# Negative_Ioniser.net
KiCad netlist of a schematic drawn in EAGLE
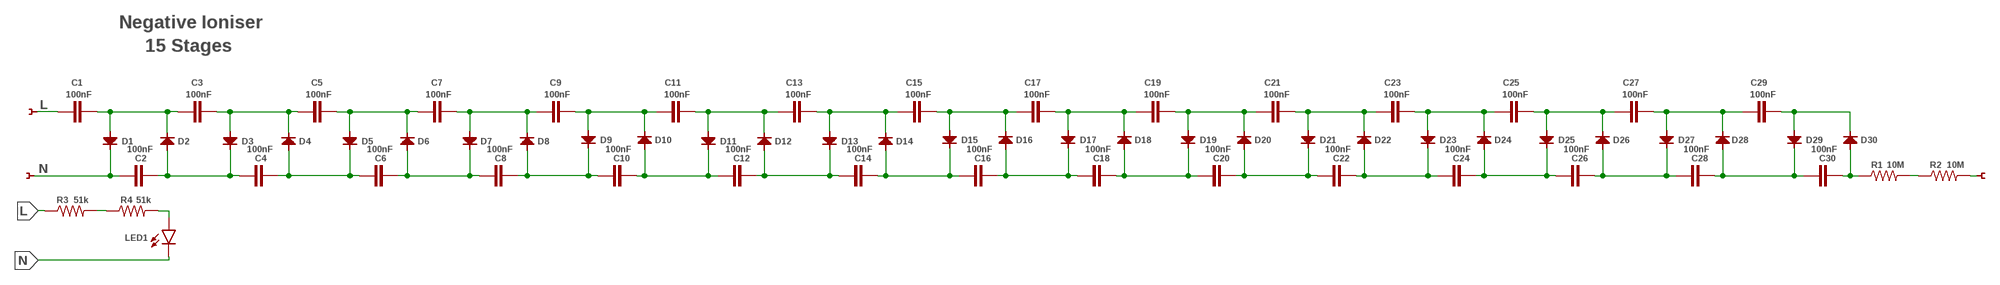
[diagram p0: schematic, sheet 1]

(export (version "E")
  (design (tool "Eeschema 10.0.6"))
  (components
    (comp (ref "C1")
      (value "100nF")
      (footprint "eagle-import:C1812")
      (fields (field (name "TOLERANCE") "±10%"))
      (libsource (lib "eagle-import") (part "CAPACITOR-1812"))
    )
    (comp (ref "C2")
      (value "100nF")
      (footprint "eagle-import:C1812")
      (fields
        (field (name "PART-NUM") "1812B104K631CT")
        (field (name "RATED") "630V")
        (field (name "TOLERANCE") "±10%")
      )
      (libsource (lib "eagle-import") (part "CAPACITOR-1812"))
    )
    (comp (ref "C3")
      (value "100nF")
      (footprint "eagle-import:C1812")
      (fields
        (field (name "PART-NUM") "1812B104K631CT")
        (field (name "RATED") "630V")
        (field (name "TOLERANCE") "±10%")
      )
      (libsource (lib "eagle-import") (part "CAPACITOR-1812"))
    )
    (comp (ref "C4")
      (value "100nF")
      (footprint "eagle-import:C1812")
      (fields
        (field (name "PART-NUM") "1812B104K631CT")
        (field (name "RATED") "630V")
        (field (name "TOLERANCE") "±10%")
      )
      (libsource (lib "eagle-import") (part "CAPACITOR-1812"))
    )
    (comp (ref "C5")
      (value "100nF")
      (footprint "eagle-import:C1812")
      (fields (field (name "TOLERANCE") "±10%"))
      (libsource (lib "eagle-import") (part "CAPACITOR-1812"))
    )
    (comp (ref "C6")
      (value "100nF")
      (footprint "eagle-import:C1812")
      (fields
        (field (name "PART-NUM") "1812B104K631CT")
        (field (name "RATED") "630V")
        (field (name "TOLERANCE") "±10%")
      )
      (libsource (lib "eagle-import") (part "CAPACITOR-1812"))
    )
    (comp (ref "C7")
      (value "100nF")
      (footprint "eagle-import:C1812")
      (fields
        (field (name "PART-NUM") "1812B104K631CT")
        (field (name "RATED") "630V")
        (field (name "TOLERANCE") "±10%")
      )
      (libsource (lib "eagle-import") (part "CAPACITOR-1812"))
    )
    (comp (ref "C8")
      (value "100nF")
      (footprint "eagle-import:C1812")
      (fields
        (field (name "PART-NUM") "1812B104K631CT")
        (field (name "RATED") "630V")
        (field (name "TOLERANCE") "±10%")
      )
      (libsource (lib "eagle-import") (part "CAPACITOR-1812"))
    )
    (comp (ref "C9")
      (value "100nF")
      (footprint "eagle-import:C1812")
      (fields (field (name "TOLERANCE") "±10%"))
      (libsource (lib "eagle-import") (part "CAPACITOR-1812"))
    )
    (comp (ref "C10")
      (value "100nF")
      (footprint "eagle-import:C1812")
      (fields
        (field (name "PART-NUM") "1812B104K631CT")
        (field (name "RATED") "630V")
        (field (name "TOLERANCE") "±10%")
      )
      (libsource (lib "eagle-import") (part "CAPACITOR-1812"))
    )
    (comp (ref "C11")
      (value "100nF")
      (footprint "eagle-import:C1812")
      (fields
        (field (name "PART-NUM") "1812B104K631CT")
        (field (name "RATED") "630V")
        (field (name "TOLERANCE") "±10%")
      )
      (libsource (lib "eagle-import") (part "CAPACITOR-1812"))
    )
    (comp (ref "C12")
      (value "100nF")
      (footprint "eagle-import:C1812")
      (fields
        (field (name "PART-NUM") "1812B104K631CT")
        (field (name "RATED") "630V")
        (field (name "TOLERANCE") "±10%")
      )
      (libsource (lib "eagle-import") (part "CAPACITOR-1812"))
    )
    (comp (ref "C13")
      (value "100nF")
      (footprint "eagle-import:C1812")
      (fields (field (name "TOLERANCE") "±10%"))
      (libsource (lib "eagle-import") (part "CAPACITOR-1812"))
    )
    (comp (ref "C14")
      (value "100nF")
      (footprint "eagle-import:C1812")
      (fields
        (field (name "PART-NUM") "1812B104K631CT")
        (field (name "RATED") "630V")
        (field (name "TOLERANCE") "±10%")
      )
      (libsource (lib "eagle-import") (part "CAPACITOR-1812"))
    )
    (comp (ref "C15")
      (value "100nF")
      (footprint "eagle-import:C1812")
      (fields
        (field (name "PART-NUM") "1812B104K631CT")
        (field (name "RATED") "630V")
        (field (name "TOLERANCE") "±10%")
      )
      (libsource (lib "eagle-import") (part "CAPACITOR-1812"))
    )
    (comp (ref "C16")
      (value "100nF")
      (footprint "eagle-import:C1812")
      (fields
        (field (name "PART-NUM") "1812B104K631CT")
        (field (name "RATED") "630V")
        (field (name "TOLERANCE") "±10%")
      )
      (libsource (lib "eagle-import") (part "CAPACITOR-1812"))
    )
    (comp (ref "C17")
      (value "100nF")
      (footprint "eagle-import:C1812")
      (fields (field (name "TOLERANCE") "±10%"))
      (libsource (lib "eagle-import") (part "CAPACITOR-1812"))
    )
    (comp (ref "C18")
      (value "100nF")
      (footprint "eagle-import:C1812")
      (fields
        (field (name "PART-NUM") "1812B104K631CT")
        (field (name "RATED") "630V")
        (field (name "TOLERANCE") "±10%")
      )
      (libsource (lib "eagle-import") (part "CAPACITOR-1812"))
    )
    (comp (ref "C19")
      (value "100nF")
      (footprint "eagle-import:C1812")
      (fields
        (field (name "PART-NUM") "1812B104K631CT")
        (field (name "RATED") "630V")
        (field (name "TOLERANCE") "±10%")
      )
      (libsource (lib "eagle-import") (part "CAPACITOR-1812"))
    )
    (comp (ref "C20")
      (value "100nF")
      (footprint "eagle-import:C1812")
      (fields
        (field (name "PART-NUM") "1812B104K631CT")
        (field (name "RATED") "630V")
        (field (name "TOLERANCE") "±10%")
      )
      (libsource (lib "eagle-import") (part "CAPACITOR-1812"))
    )
    (comp (ref "C21")
      (value "100nF")
      (footprint "eagle-import:C1812")
      (fields (field (name "TOLERANCE") "±10%"))
      (libsource (lib "eagle-import") (part "CAPACITOR-1812"))
    )
    (comp (ref "C22")
      (value "100nF")
      (footprint "eagle-import:C1812")
      (fields
        (field (name "PART-NUM") "1812B104K631CT")
        (field (name "RATED") "630V")
        (field (name "TOLERANCE") "±10%")
      )
      (libsource (lib "eagle-import") (part "CAPACITOR-1812"))
    )
    (comp (ref "C23")
      (value "100nF")
      (footprint "eagle-import:C1812")
      (fields
        (field (name "PART-NUM") "1812B104K631CT")
        (field (name "RATED") "630V")
        (field (name "TOLERANCE") "±10%")
      )
      (libsource (lib "eagle-import") (part "CAPACITOR-1812"))
    )
    (comp (ref "C24")
      (value "100nF")
      (footprint "eagle-import:C1812")
      (fields
        (field (name "PART-NUM") "1812B104K631CT")
        (field (name "RATED") "630V")
        (field (name "TOLERANCE") "±10%")
      )
      (libsource (lib "eagle-import") (part "CAPACITOR-1812"))
    )
    (comp (ref "C25")
      (value "100nF")
      (footprint "eagle-import:C1812")
      (fields (field (name "TOLERANCE") "±10%"))
      (libsource (lib "eagle-import") (part "CAPACITOR-1812"))
    )
    (comp (ref "C26")
      (value "100nF")
      (footprint "eagle-import:C1812")
      (fields
        (field (name "PART-NUM") "1812B104K631CT")
        (field (name "RATED") "630V")
        (field (name "TOLERANCE") "±10%")
      )
      (libsource (lib "eagle-import") (part "CAPACITOR-1812"))
    )
    (comp (ref "C27")
      (value "100nF")
      (footprint "eagle-import:C1812")
      (fields
        (field (name "PART-NUM") "1812B104K631CT")
        (field (name "RATED") "630V")
        (field (name "TOLERANCE") "±10%")
      )
      (libsource (lib "eagle-import") (part "CAPACITOR-1812"))
    )
    (comp (ref "C28")
      (value "100nF")
      (footprint "eagle-import:C1812")
      (fields
        (field (name "PART-NUM") "1812B104K631CT")
        (field (name "RATED") "630V")
        (field (name "TOLERANCE") "±10%")
      )
      (libsource (lib "eagle-import") (part "CAPACITOR-1812"))
    )
    (comp (ref "C29")
      (value "100nF")
      (footprint "eagle-import:C1812")
      (fields
        (field (name "PART-NUM") "1812B104K631CT")
        (field (name "RATED") "630V")
        (field (name "TOLERANCE") "±10%")
      )
      (libsource (lib "eagle-import") (part "CAPACITOR-1812"))
    )
    (comp (ref "C30")
      (value "100nF")
      (footprint "eagle-import:C1812")
      (fields
        (field (name "PART-NUM") "1812B104K631CT")
        (field (name "RATED") "630V")
        (field (name "TOLERANCE") "±10%")
      )
      (libsource (lib "eagle-import") (part "CAPACITOR-1812"))
    )
    (comp (ref "D1")
      (value "DIODE-1N4007")
      (footprint "eagle-import:DO-214A")
      (fields
        (field (name "I-RATING") "1A")
        (field (name "PART-NUM") "1N4007G")
        (field (name "V-RATING") "1kV")
      )
      (libsource (lib "eagle-import") (part "DIODE-1N4007"))
    )
    (comp (ref "D2")
      (value "DIODE-1N4007")
      (footprint "eagle-import:DO-214A")
      (fields
        (field (name "I-RATING") "1A")
        (field (name "PART-NUM") "1N4007G")
        (field (name "V-RATING") "1kV")
      )
      (libsource (lib "eagle-import") (part "DIODE-1N4007"))
    )
    (comp (ref "D3")
      (value "DIODE-1N4007")
      (footprint "eagle-import:DO-214A")
      (fields
        (field (name "I-RATING") "1A")
        (field (name "PART-NUM") "1N4007G")
        (field (name "V-RATING") "1kV")
      )
      (libsource (lib "eagle-import") (part "DIODE-1N4007"))
    )
    (comp (ref "D4")
      (value "DIODE-1N4007")
      (footprint "eagle-import:DO-214A")
      (fields
        (field (name "I-RATING") "1A")
        (field (name "PART-NUM") "1N4007G")
        (field (name "V-RATING") "1kV")
      )
      (libsource (lib "eagle-import") (part "DIODE-1N4007"))
    )
    (comp (ref "D5")
      (value "DIODE-1N4007")
      (footprint "eagle-import:DO-214A")
      (fields
        (field (name "I-RATING") "1A")
        (field (name "PART-NUM") "1N4007G")
        (field (name "V-RATING") "1kV")
      )
      (libsource (lib "eagle-import") (part "DIODE-1N4007"))
    )
    (comp (ref "D6")
      (value "DIODE-1N4007")
      (footprint "eagle-import:DO-214A")
      (fields
        (field (name "I-RATING") "1A")
        (field (name "PART-NUM") "1N4007G")
        (field (name "V-RATING") "1kV")
      )
      (libsource (lib "eagle-import") (part "DIODE-1N4007"))
    )
    (comp (ref "D7")
      (value "DIODE-1N4007")
      (footprint "eagle-import:DO-214A")
      (fields
        (field (name "I-RATING") "1A")
        (field (name "PART-NUM") "1N4007G")
        (field (name "V-RATING") "1kV")
      )
      (libsource (lib "eagle-import") (part "DIODE-1N4007"))
    )
    (comp (ref "D8")
      (value "DIODE-1N4007")
      (footprint "eagle-import:DO-214A")
      (fields
        (field (name "I-RATING") "1A")
        (field (name "PART-NUM") "1N4007G")
        (field (name "V-RATING") "1kV")
      )
      (libsource (lib "eagle-import") (part "DIODE-1N4007"))
    )
    (comp (ref "D9")
      (value "DIODE-1N4007")
      (footprint "eagle-import:DO-214A")
      (fields
        (field (name "I-RATING") "1A")
        (field (name "PART-NUM") "1N4007G")
        (field (name "V-RATING") "1kV")
      )
      (libsource (lib "eagle-import") (part "DIODE-1N4007"))
    )
    (comp (ref "D10")
      (value "DIODE-1N4007")
      (footprint "eagle-import:DO-214A")
      (fields
        (field (name "I-RATING") "1A")
        (field (name "PART-NUM") "1N4007G")
        (field (name "V-RATING") "1kV")
      )
      (libsource (lib "eagle-import") (part "DIODE-1N4007"))
    )
    (comp (ref "D11")
      (value "DIODE-1N4007")
      (footprint "eagle-import:DO-214A")
      (fields
        (field (name "I-RATING") "1A")
        (field (name "PART-NUM") "1N4007G")
        (field (name "V-RATING") "1kV")
      )
      (libsource (lib "eagle-import") (part "DIODE-1N4007"))
    )
    (comp (ref "D12")
      (value "DIODE-1N4007")
      (footprint "eagle-import:DO-214A")
      (fields
        (field (name "I-RATING") "1A")
        (field (name "PART-NUM") "1N4007G")
        (field (name "V-RATING") "1kV")
      )
      (libsource (lib "eagle-import") (part "DIODE-1N4007"))
    )
    (comp (ref "D13")
      (value "DIODE-1N4007")
      (footprint "eagle-import:DO-214A")
      (fields
        (field (name "I-RATING") "1A")
        (field (name "PART-NUM") "1N4007G")
        (field (name "V-RATING") "1kV")
      )
      (libsource (lib "eagle-import") (part "DIODE-1N4007"))
    )
    (comp (ref "D14")
      (value "DIODE-1N4007")
      (footprint "eagle-import:DO-214A")
      (fields
        (field (name "I-RATING") "1A")
        (field (name "PART-NUM") "1N4007G")
        (field (name "V-RATING") "1kV")
      )
      (libsource (lib "eagle-import") (part "DIODE-1N4007"))
    )
    (comp (ref "D15")
      (value "DIODE-1N4007")
      (footprint "eagle-import:DO-214A")
      (fields
        (field (name "I-RATING") "1A")
        (field (name "PART-NUM") "1N4007G")
        (field (name "V-RATING") "1kV")
      )
      (libsource (lib "eagle-import") (part "DIODE-1N4007"))
    )
    (comp (ref "D16")
      (value "DIODE-1N4007")
      (footprint "eagle-import:DO-214A")
      (fields
        (field (name "I-RATING") "1A")
        (field (name "PART-NUM") "1N4007G")
        (field (name "V-RATING") "1kV")
      )
      (libsource (lib "eagle-import") (part "DIODE-1N4007"))
    )
    (comp (ref "D17")
      (value "DIODE-1N4007")
      (footprint "eagle-import:DO-214A")
      (fields
        (field (name "I-RATING") "1A")
        (field (name "PART-NUM") "1N4007G")
        (field (name "V-RATING") "1kV")
      )
      (libsource (lib "eagle-import") (part "DIODE-1N4007"))
    )
    (comp (ref "D18")
      (value "DIODE-1N4007")
      (footprint "eagle-import:DO-214A")
      (fields
        (field (name "I-RATING") "1A")
        (field (name "PART-NUM") "1N4007G")
        (field (name "V-RATING") "1kV")
      )
      (libsource (lib "eagle-import") (part "DIODE-1N4007"))
    )
    (comp (ref "D19")
      (value "DIODE-1N4007")
      (footprint "eagle-import:DO-214A")
      (fields
        (field (name "I-RATING") "1A")
        (field (name "PART-NUM") "1N4007G")
        (field (name "V-RATING") "1kV")
      )
      (libsource (lib "eagle-import") (part "DIODE-1N4007"))
    )
    (comp (ref "D20")
      (value "DIODE-1N4007")
      (footprint "eagle-import:DO-214A")
      (fields
        (field (name "I-RATING") "1A")
        (field (name "PART-NUM") "1N4007G")
        (field (name "V-RATING") "1kV")
      )
      (libsource (lib "eagle-import") (part "DIODE-1N4007"))
    )
    (comp (ref "D21")
      (value "DIODE-1N4007")
      (footprint "eagle-import:DO-214A")
      (fields
        (field (name "I-RATING") "1A")
        (field (name "PART-NUM") "1N4007G")
        (field (name "V-RATING") "1kV")
      )
      (libsource (lib "eagle-import") (part "DIODE-1N4007"))
    )
    (comp (ref "D22")
      (value "DIODE-1N4007")
      (footprint "eagle-import:DO-214A")
      (fields
        (field (name "I-RATING") "1A")
        (field (name "PART-NUM") "1N4007G")
        (field (name "V-RATING") "1kV")
      )
      (libsource (lib "eagle-import") (part "DIODE-1N4007"))
    )
    (comp (ref "D23")
      (value "DIODE-1N4007")
      (footprint "eagle-import:DO-214A")
      (fields
        (field (name "I-RATING") "1A")
        (field (name "PART-NUM") "1N4007G")
        (field (name "V-RATING") "1kV")
      )
      (libsource (lib "eagle-import") (part "DIODE-1N4007"))
    )
    (comp (ref "D24")
      (value "DIODE-1N4007")
      (footprint "eagle-import:DO-214A")
      (fields
        (field (name "I-RATING") "1A")
        (field (name "PART-NUM") "1N4007G")
        (field (name "V-RATING") "1kV")
      )
      (libsource (lib "eagle-import") (part "DIODE-1N4007"))
    )
    (comp (ref "D25")
      (value "DIODE-1N4007")
      (footprint "eagle-import:DO-214A")
      (fields
        (field (name "I-RATING") "1A")
        (field (name "PART-NUM") "1N4007G")
        (field (name "V-RATING") "1kV")
      )
      (libsource (lib "eagle-import") (part "DIODE-1N4007"))
    )
    (comp (ref "D26")
      (value "DIODE-1N4007")
      (footprint "eagle-import:DO-214A")
      (fields
        (field (name "I-RATING") "1A")
        (field (name "PART-NUM") "1N4007G")
        (field (name "V-RATING") "1kV")
      )
      (libsource (lib "eagle-import") (part "DIODE-1N4007"))
    )
    (comp (ref "D27")
      (value "DIODE-1N4007")
      (footprint "eagle-import:DO-214A")
      (fields
        (field (name "I-RATING") "1A")
        (field (name "PART-NUM") "1N4007G")
        (field (name "V-RATING") "1kV")
      )
      (libsource (lib "eagle-import") (part "DIODE-1N4007"))
    )
    (comp (ref "D28")
      (value "DIODE-1N4007")
      (footprint "eagle-import:DO-214A")
      (fields
        (field (name "I-RATING") "1A")
        (field (name "PART-NUM") "1N4007G")
        (field (name "V-RATING") "1kV")
      )
      (libsource (lib "eagle-import") (part "DIODE-1N4007"))
    )
    (comp (ref "D29")
      (value "DIODE-1N4007")
      (footprint "eagle-import:DO-214A")
      (fields
        (field (name "I-RATING") "1A")
        (field (name "PART-NUM") "1N4007G")
        (field (name "V-RATING") "1kV")
      )
      (libsource (lib "eagle-import") (part "DIODE-1N4007"))
    )
    (comp (ref "D30")
      (value "DIODE-1N4007")
      (footprint "eagle-import:DO-214A")
      (fields
        (field (name "I-RATING") "1A")
        (field (name "PART-NUM") "1N4007G")
        (field (name "V-RATING") "1kV")
      )
      (libsource (lib "eagle-import") (part "DIODE-1N4007"))
    )
    (comp (ref "LED1")
      (value "LED-0603-SMD")
      (footprint "eagle-import:LED-0603")
      (fields (field (name "PART-NUM") "D-060306R1/SS2/L"))
      (libsource (lib "eagle-import") (part "LED-0603-SMD"))
    )
    (comp (ref "R1")
      (value "10M")
      (footprint "eagle-import:R1206")
      (fields
        (field (name "PART-NUM") "1206W4F1005T5E")
        (field (name "RATED") "0.25W")
        (field (name "TOLERANCE") "±1%")
      )
      (libsource (lib "eagle-import") (part "RESISTOR-1206"))
    )
    (comp (ref "R2")
      (value "10M")
      (footprint "eagle-import:R1206")
      (fields
        (field (name "PART-NUM") "1206W4F1005T5E")
        (field (name "RATED") "0.25W")
        (field (name "TOLERANCE") "±1%")
      )
      (libsource (lib "eagle-import") (part "RESISTOR-1206"))
    )
    (comp (ref "R3")
      (value "51k")
      (footprint "eagle-import:R1210")
      (fields
        (field (name "PART-NUM") "CR1210J51K0P05Z")
        (field (name "RATED") "0.5W")
        (field (name "TOLERANCE") "±5%")
      )
      (libsource (lib "eagle-import") (part "RESISTOR-1210"))
    )
    (comp (ref "R4")
      (value "51k")
      (footprint "eagle-import:R1210")
      (fields
        (field (name "PART-NUM") "CR1210J51K0P05Z")
        (field (name "RATED") "0.5W")
        (field (name "TOLERANCE") "±5%")
      )
      (libsource (lib "eagle-import") (part "RESISTOR-1210"))
    )
    (comp (ref "TP1")
      (value "TEST-POINT5MM")
      (footprint "eagle-import:SMD-SQ-PADS-5MM")
      (libsource (lib "eagle-import") (part "TEST-POINT5MM"))
    )
    (comp (ref "TP2")
      (value "TEST-POINT5MM")
      (footprint "eagle-import:SMD-SQ-PADS-5MM")
      (libsource (lib "eagle-import") (part "TEST-POINT5MM"))
    )
    (comp (ref "TP3")
      (value "TEST-POINT30X10")
      (footprint "eagle-import:LONG-RECT-PAD-50MM")
      (libsource (lib "eagle-import") (part "TEST-POINT30X10"))
    )
  )
  (nets
    (net (code "1") (name "L") (class "Default")
      (node (ref "C1") (pin "1") (pinfunction "1_1") (pintype "passive"))
      (node (ref "R3") (pin "1") (pinfunction "1_1") (pintype "passive"))
      (node (ref "TP1") (pin "P$1") (pinfunction "1_P$1") (pintype "bidirectional"))
    )
    (net (code "2") (name "N") (class "Default")
      (node (ref "C2") (pin "1") (pinfunction "1_1") (pintype "passive"))
      (node (ref "D1") (pin "CATHODE") (pinfunction "C_CATHODE") (pintype "bidirectional"))
      (node (ref "LED1") (pin "C") (pinfunction "C_C") (pintype "passive"))
      (node (ref "TP2") (pin "P$1") (pinfunction "1_P$1") (pintype "bidirectional"))
    )
    (net (code "3") (name "Net-(D1-A)") (class "Default")
      (node (ref "C1") (pin "2") (pinfunction "2_2") (pintype "passive"))
      (node (ref "C3") (pin "1") (pinfunction "1_1") (pintype "passive"))
      (node (ref "D1") (pin "ANODE") (pinfunction "A_ANODE") (pintype "bidirectional"))
      (node (ref "D2") (pin "CATHODE") (pinfunction "C_CATHODE") (pintype "bidirectional"))
    )
    (net (code "4") (name "Net-(D2-A)") (class "Default")
      (node (ref "C2") (pin "2") (pinfunction "2_2") (pintype "passive"))
      (node (ref "C4") (pin "1") (pinfunction "1_1") (pintype "passive"))
      (node (ref "D2") (pin "ANODE") (pinfunction "A_ANODE") (pintype "bidirectional"))
      (node (ref "D3") (pin "CATHODE") (pinfunction "C_CATHODE") (pintype "bidirectional"))
    )
    (net (code "5") (name "Net-(D3-A)") (class "Default")
      (node (ref "C3") (pin "2") (pinfunction "2_2") (pintype "passive"))
      (node (ref "C5") (pin "1") (pinfunction "1_1") (pintype "passive"))
      (node (ref "D3") (pin "ANODE") (pinfunction "A_ANODE") (pintype "bidirectional"))
      (node (ref "D4") (pin "CATHODE") (pinfunction "C_CATHODE") (pintype "bidirectional"))
    )
    (net (code "6") (name "Net-(D4-A)") (class "Default")
      (node (ref "C4") (pin "2") (pinfunction "2_2") (pintype "passive"))
      (node (ref "C6") (pin "1") (pinfunction "1_1") (pintype "passive"))
      (node (ref "D4") (pin "ANODE") (pinfunction "A_ANODE") (pintype "bidirectional"))
      (node (ref "D5") (pin "CATHODE") (pinfunction "C_CATHODE") (pintype "bidirectional"))
    )
    (net (code "7") (name "Net-(D5-A)") (class "Default")
      (node (ref "C5") (pin "2") (pinfunction "2_2") (pintype "passive"))
      (node (ref "C7") (pin "1") (pinfunction "1_1") (pintype "passive"))
      (node (ref "D5") (pin "ANODE") (pinfunction "A_ANODE") (pintype "bidirectional"))
      (node (ref "D6") (pin "CATHODE") (pinfunction "C_CATHODE") (pintype "bidirectional"))
    )
    (net (code "8") (name "Net-(D6-A)") (class "Default")
      (node (ref "C6") (pin "2") (pinfunction "2_2") (pintype "passive"))
      (node (ref "C8") (pin "1") (pinfunction "1_1") (pintype "passive"))
      (node (ref "D6") (pin "ANODE") (pinfunction "A_ANODE") (pintype "bidirectional"))
      (node (ref "D7") (pin "CATHODE") (pinfunction "C_CATHODE") (pintype "bidirectional"))
    )
    (net (code "9") (name "Net-(D7-A)") (class "Default")
      (node (ref "C7") (pin "2") (pinfunction "2_2") (pintype "passive"))
      (node (ref "C9") (pin "1") (pinfunction "1_1") (pintype "passive"))
      (node (ref "D7") (pin "ANODE") (pinfunction "A_ANODE") (pintype "bidirectional"))
      (node (ref "D8") (pin "CATHODE") (pinfunction "C_CATHODE") (pintype "bidirectional"))
    )
    (net (code "10") (name "Net-(D8-A)") (class "Default")
      (node (ref "C10") (pin "1") (pinfunction "1_1") (pintype "passive"))
      (node (ref "C8") (pin "2") (pinfunction "2_2") (pintype "passive"))
      (node (ref "D8") (pin "ANODE") (pinfunction "A_ANODE") (pintype "bidirectional"))
      (node (ref "D9") (pin "CATHODE") (pinfunction "C_CATHODE") (pintype "bidirectional"))
    )
    (net (code "11") (name "Net-(D10-A)") (class "Default")
      (node (ref "C10") (pin "2") (pinfunction "2_2") (pintype "passive"))
      (node (ref "C12") (pin "1") (pinfunction "1_1") (pintype "passive"))
      (node (ref "D10") (pin "ANODE") (pinfunction "A_ANODE") (pintype "bidirectional"))
      (node (ref "D11") (pin "CATHODE") (pinfunction "C_CATHODE") (pintype "bidirectional"))
    )
    (net (code "12") (name "Net-(D10-C)") (class "Default")
      (node (ref "C11") (pin "1") (pinfunction "1_1") (pintype "passive"))
      (node (ref "C9") (pin "2") (pinfunction "2_2") (pintype "passive"))
      (node (ref "D10") (pin "CATHODE") (pinfunction "C_CATHODE") (pintype "bidirectional"))
      (node (ref "D9") (pin "ANODE") (pinfunction "A_ANODE") (pintype "bidirectional"))
    )
    (net (code "13") (name "Net-(D11-A)") (class "Default")
      (node (ref "C11") (pin "2") (pinfunction "2_2") (pintype "passive"))
      (node (ref "C13") (pin "1") (pinfunction "1_1") (pintype "passive"))
      (node (ref "D11") (pin "ANODE") (pinfunction "A_ANODE") (pintype "bidirectional"))
      (node (ref "D12") (pin "CATHODE") (pinfunction "C_CATHODE") (pintype "bidirectional"))
    )
    (net (code "14") (name "Net-(D12-A)") (class "Default")
      (node (ref "C12") (pin "2") (pinfunction "2_2") (pintype "passive"))
      (node (ref "C14") (pin "1") (pinfunction "1_1") (pintype "passive"))
      (node (ref "D12") (pin "ANODE") (pinfunction "A_ANODE") (pintype "bidirectional"))
      (node (ref "D13") (pin "CATHODE") (pinfunction "C_CATHODE") (pintype "bidirectional"))
    )
    (net (code "15") (name "Net-(D13-A)") (class "Default")
      (node (ref "C13") (pin "2") (pinfunction "2_2") (pintype "passive"))
      (node (ref "C15") (pin "1") (pinfunction "1_1") (pintype "passive"))
      (node (ref "D13") (pin "ANODE") (pinfunction "A_ANODE") (pintype "bidirectional"))
      (node (ref "D14") (pin "CATHODE") (pinfunction "C_CATHODE") (pintype "bidirectional"))
    )
    (net (code "16") (name "Net-(D14-A)") (class "Default")
      (node (ref "C14") (pin "2") (pinfunction "2_2") (pintype "passive"))
      (node (ref "C16") (pin "1") (pinfunction "1_1") (pintype "passive"))
      (node (ref "D14") (pin "ANODE") (pinfunction "A_ANODE") (pintype "bidirectional"))
      (node (ref "D15") (pin "CATHODE") (pinfunction "C_CATHODE") (pintype "bidirectional"))
    )
    (net (code "17") (name "Net-(D15-A)") (class "Default")
      (node (ref "C15") (pin "2") (pinfunction "2_2") (pintype "passive"))
      (node (ref "C17") (pin "1") (pinfunction "1_1") (pintype "passive"))
      (node (ref "D15") (pin "ANODE") (pinfunction "A_ANODE") (pintype "bidirectional"))
      (node (ref "D16") (pin "CATHODE") (pinfunction "C_CATHODE") (pintype "bidirectional"))
    )
    (net (code "18") (name "Net-(D16-A)") (class "Default")
      (node (ref "C16") (pin "2") (pinfunction "2_2") (pintype "passive"))
      (node (ref "C18") (pin "1") (pinfunction "1_1") (pintype "passive"))
      (node (ref "D16") (pin "ANODE") (pinfunction "A_ANODE") (pintype "bidirectional"))
      (node (ref "D17") (pin "CATHODE") (pinfunction "C_CATHODE") (pintype "bidirectional"))
    )
    (net (code "19") (name "Net-(D17-A)") (class "Default")
      (node (ref "C17") (pin "2") (pinfunction "2_2") (pintype "passive"))
      (node (ref "C19") (pin "1") (pinfunction "1_1") (pintype "passive"))
      (node (ref "D17") (pin "ANODE") (pinfunction "A_ANODE") (pintype "bidirectional"))
      (node (ref "D18") (pin "CATHODE") (pinfunction "C_CATHODE") (pintype "bidirectional"))
    )
    (net (code "20") (name "Net-(D18-A)") (class "Default")
      (node (ref "C18") (pin "2") (pinfunction "2_2") (pintype "passive"))
      (node (ref "C20") (pin "1") (pinfunction "1_1") (pintype "passive"))
      (node (ref "D18") (pin "ANODE") (pinfunction "A_ANODE") (pintype "bidirectional"))
      (node (ref "D19") (pin "CATHODE") (pinfunction "C_CATHODE") (pintype "bidirectional"))
    )
    (net (code "21") (name "Net-(D19-A)") (class "Default")
      (node (ref "C19") (pin "2") (pinfunction "2_2") (pintype "passive"))
      (node (ref "C21") (pin "1") (pinfunction "1_1") (pintype "passive"))
      (node (ref "D19") (pin "ANODE") (pinfunction "A_ANODE") (pintype "bidirectional"))
      (node (ref "D20") (pin "CATHODE") (pinfunction "C_CATHODE") (pintype "bidirectional"))
    )
    (net (code "22") (name "Net-(D20-A)") (class "Default")
      (node (ref "C20") (pin "2") (pinfunction "2_2") (pintype "passive"))
      (node (ref "C22") (pin "1") (pinfunction "1_1") (pintype "passive"))
      (node (ref "D20") (pin "ANODE") (pinfunction "A_ANODE") (pintype "bidirectional"))
      (node (ref "D21") (pin "CATHODE") (pinfunction "C_CATHODE") (pintype "bidirectional"))
    )
    (net (code "23") (name "Net-(D21-A)") (class "Default")
      (node (ref "C21") (pin "2") (pinfunction "2_2") (pintype "passive"))
      (node (ref "C23") (pin "1") (pinfunction "1_1") (pintype "passive"))
      (node (ref "D21") (pin "ANODE") (pinfunction "A_ANODE") (pintype "bidirectional"))
      (node (ref "D22") (pin "CATHODE") (pinfunction "C_CATHODE") (pintype "bidirectional"))
    )
    (net (code "24") (name "Net-(D22-A)") (class "Default")
      (node (ref "C22") (pin "2") (pinfunction "2_2") (pintype "passive"))
      (node (ref "C24") (pin "1") (pinfunction "1_1") (pintype "passive"))
      (node (ref "D22") (pin "ANODE") (pinfunction "A_ANODE") (pintype "bidirectional"))
      (node (ref "D23") (pin "CATHODE") (pinfunction "C_CATHODE") (pintype "bidirectional"))
    )
    (net (code "25") (name "Net-(D23-A)") (class "Default")
      (node (ref "C23") (pin "2") (pinfunction "2_2") (pintype "passive"))
      (node (ref "C25") (pin "1") (pinfunction "1_1") (pintype "passive"))
      (node (ref "D23") (pin "ANODE") (pinfunction "A_ANODE") (pintype "bidirectional"))
      (node (ref "D24") (pin "CATHODE") (pinfunction "C_CATHODE") (pintype "bidirectional"))
    )
    (net (code "26") (name "Net-(D24-A)") (class "Default")
      (node (ref "C24") (pin "2") (pinfunction "2_2") (pintype "passive"))
      (node (ref "C26") (pin "1") (pinfunction "1_1") (pintype "passive"))
      (node (ref "D24") (pin "ANODE") (pinfunction "A_ANODE") (pintype "bidirectional"))
      (node (ref "D25") (pin "CATHODE") (pinfunction "C_CATHODE") (pintype "bidirectional"))
    )
    (net (code "27") (name "Net-(D25-A)") (class "Default")
      (node (ref "C25") (pin "2") (pinfunction "2_2") (pintype "passive"))
      (node (ref "C27") (pin "1") (pinfunction "1_1") (pintype "passive"))
      (node (ref "D25") (pin "ANODE") (pinfunction "A_ANODE") (pintype "bidirectional"))
      (node (ref "D26") (pin "CATHODE") (pinfunction "C_CATHODE") (pintype "bidirectional"))
    )
    (net (code "28") (name "Net-(D26-A)") (class "Default")
      (node (ref "C26") (pin "2") (pinfunction "2_2") (pintype "passive"))
      (node (ref "C28") (pin "1") (pinfunction "1_1") (pintype "passive"))
      (node (ref "D26") (pin "ANODE") (pinfunction "A_ANODE") (pintype "bidirectional"))
      (node (ref "D27") (pin "CATHODE") (pinfunction "C_CATHODE") (pintype "bidirectional"))
    )
    (net (code "29") (name "Net-(D27-A)") (class "Default")
      (node (ref "C27") (pin "2") (pinfunction "2_2") (pintype "passive"))
      (node (ref "C29") (pin "1") (pinfunction "1_1") (pintype "passive"))
      (node (ref "D27") (pin "ANODE") (pinfunction "A_ANODE") (pintype "bidirectional"))
      (node (ref "D28") (pin "CATHODE") (pinfunction "C_CATHODE") (pintype "bidirectional"))
    )
    (net (code "30") (name "Net-(D28-A)") (class "Default")
      (node (ref "C28") (pin "2") (pinfunction "2_2") (pintype "passive"))
      (node (ref "C30") (pin "1") (pinfunction "1_1") (pintype "passive"))
      (node (ref "D28") (pin "ANODE") (pinfunction "A_ANODE") (pintype "bidirectional"))
      (node (ref "D29") (pin "CATHODE") (pinfunction "C_CATHODE") (pintype "bidirectional"))
    )
    (net (code "31") (name "Net-(D29-A)") (class "Default")
      (node (ref "C29") (pin "2") (pinfunction "2_2") (pintype "passive"))
      (node (ref "D29") (pin "ANODE") (pinfunction "A_ANODE") (pintype "bidirectional"))
      (node (ref "D30") (pin "CATHODE") (pinfunction "C_CATHODE") (pintype "bidirectional"))
    )
    (net (code "32") (name "Net-(D30-A)") (class "Default")
      (node (ref "C30") (pin "2") (pinfunction "2_2") (pintype "passive"))
      (node (ref "D30") (pin "ANODE") (pinfunction "A_ANODE") (pintype "bidirectional"))
      (node (ref "R1") (pin "1") (pinfunction "1_1") (pintype "passive"))
    )
    (net (code "33") (name "Net-(LED1-PadA)") (class "Default")
      (node (ref "LED1") (pin "A") (pinfunction "A_A") (pintype "passive"))
      (node (ref "R4") (pin "2") (pinfunction "2_2") (pintype "passive"))
    )
    (net (code "34") (name "Net-(R1-Pad2)") (class "Default")
      (node (ref "R1") (pin "2") (pinfunction "2_2") (pintype "passive"))
      (node (ref "R2") (pin "1") (pinfunction "1_1") (pintype "passive"))
    )
    (net (code "35") (name "Net-(R2-Pad2)") (class "Default")
      (node (ref "R2") (pin "2") (pinfunction "2_2") (pintype "passive"))
      (node (ref "TP3") (pin "1") (pinfunction "1_1") (pintype "bidirectional"))
    )
    (net (code "36") (name "Net-(R3-Pad2)") (class "Default")
      (node (ref "R3") (pin "2") (pinfunction "2_2") (pintype "passive"))
      (node (ref "R4") (pin "1") (pinfunction "1_1") (pintype "passive"))
    )
  )
)
